# RoverBaseboard.net
KiCad netlist of a schematic drawn in EAGLE
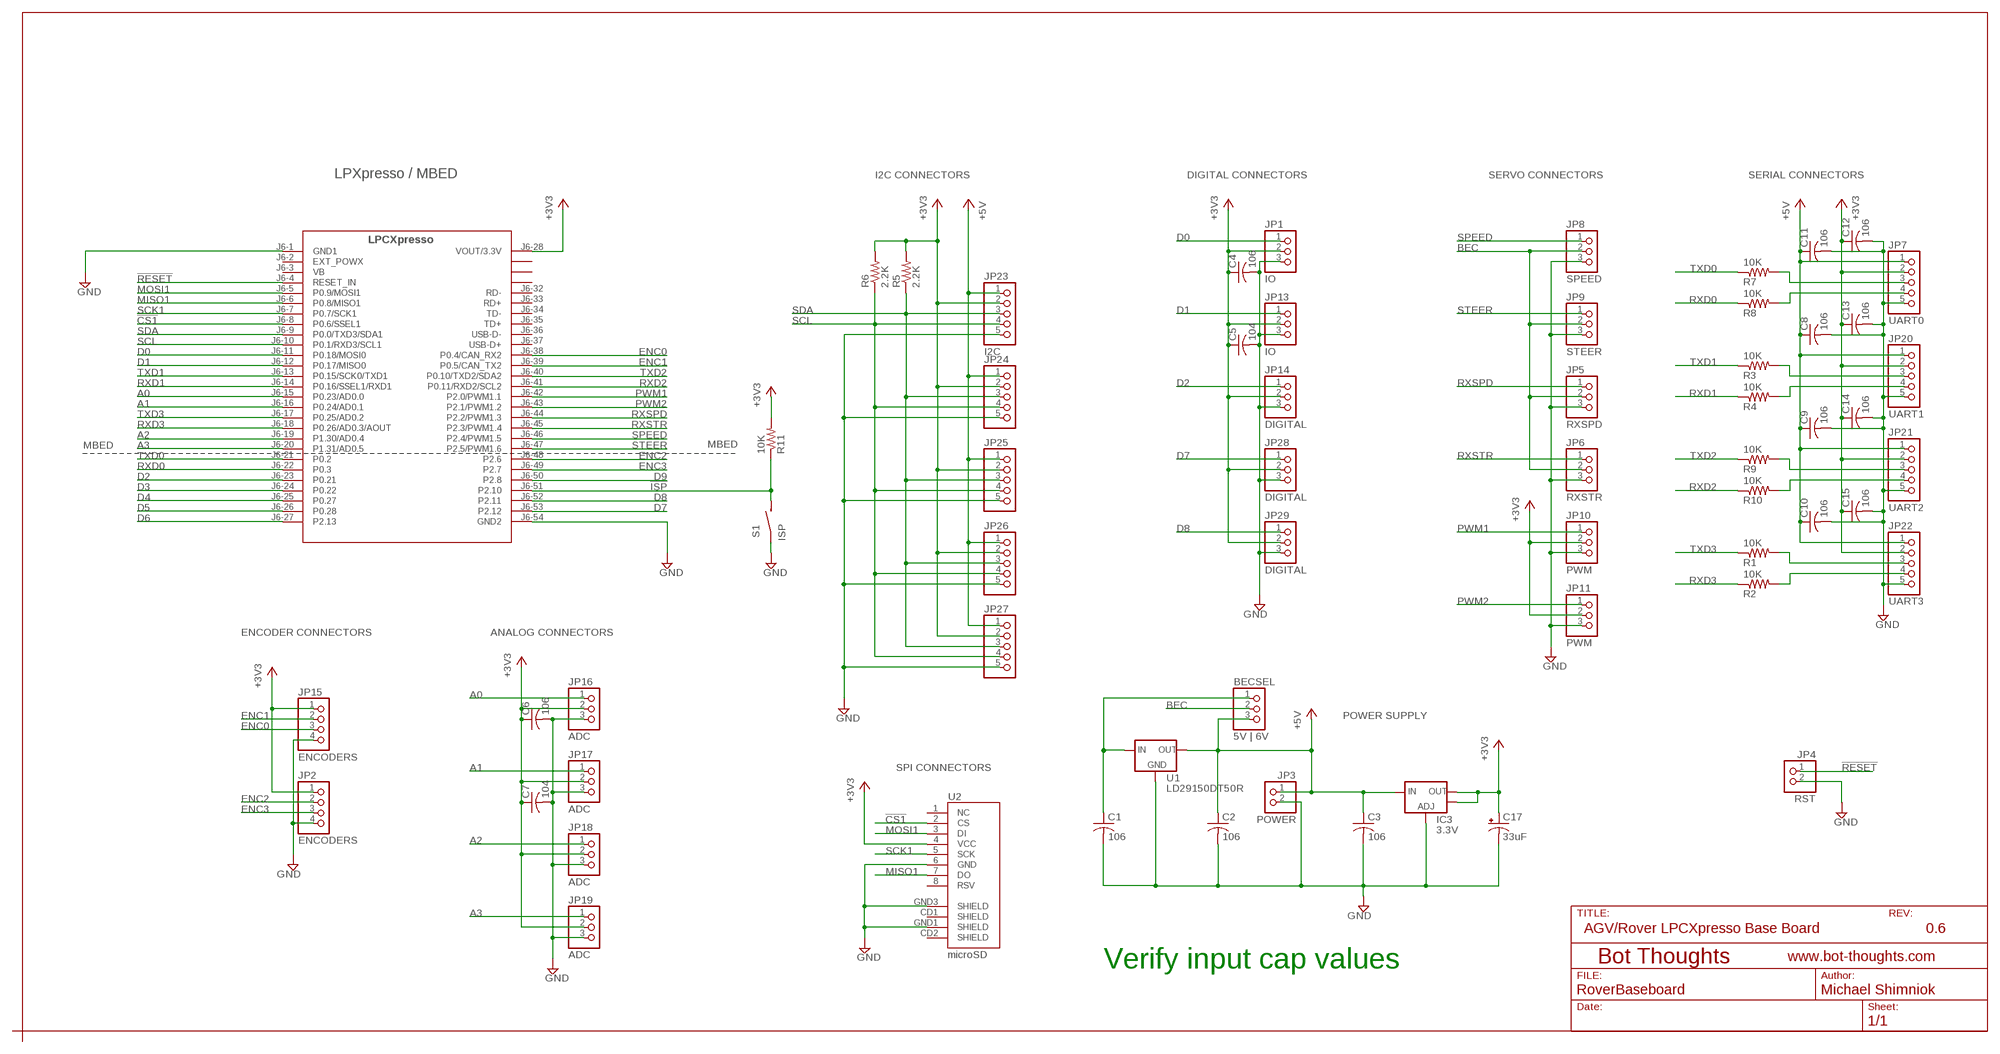
[diagram p0: schematic, sheet 1]

(export (version "E")
  (design (tool "Eeschema 10.0.6"))
  (components
    (comp (ref "BECSEL")
      (value "5V | 6V")
      (footprint "eagle-import:1X03-S")
      (libsource (lib "eagle-import") (part "PINHD-1X03_2.54-S"))
    )
    (comp (ref "C1")
      (value "106")
      (footprint "eagle-import:C1206")
      (libsource (lib "eagle-import") (part "C-USC1206"))
    )
    (comp (ref "C2")
      (value "106")
      (footprint "eagle-import:C1206")
      (libsource (lib "eagle-import") (part "C-USC1206"))
    )
    (comp (ref "C3")
      (value "106")
      (footprint "eagle-import:C1206")
      (libsource (lib "eagle-import") (part "C-USC1206"))
    )
    (comp (ref "C4")
      (value "106")
      (footprint "eagle-import:C0603")
      (libsource (lib "eagle-import") (part "C-USC0603"))
    )
    (comp (ref "C5")
      (value "104")
      (footprint "eagle-import:C0603")
      (libsource (lib "eagle-import") (part "C-USC0603"))
    )
    (comp (ref "C6")
      (value "106")
      (footprint "eagle-import:C0603")
      (libsource (lib "eagle-import") (part "C-USC0603"))
    )
    (comp (ref "C7")
      (value "104")
      (footprint "eagle-import:C0603")
      (libsource (lib "eagle-import") (part "C-USC0603"))
    )
    (comp (ref "C8")
      (value "106")
      (footprint "eagle-import:C0603")
      (libsource (lib "eagle-import") (part "C-USC0603"))
    )
    (comp (ref "C9")
      (value "106")
      (footprint "eagle-import:C0603")
      (libsource (lib "eagle-import") (part "C-USC0603"))
    )
    (comp (ref "C10")
      (value "106")
      (footprint "eagle-import:C0603")
      (libsource (lib "eagle-import") (part "C-USC0603"))
    )
    (comp (ref "C11")
      (value "106")
      (footprint "eagle-import:C0603")
      (libsource (lib "eagle-import") (part "C-USC0603"))
    )
    (comp (ref "C12")
      (value "106")
      (footprint "eagle-import:C0603")
      (libsource (lib "eagle-import") (part "C-USC0603"))
    )
    (comp (ref "C13")
      (value "106")
      (footprint "eagle-import:C0603")
      (libsource (lib "eagle-import") (part "C-USC0603"))
    )
    (comp (ref "C14")
      (value "106")
      (footprint "eagle-import:C0603")
      (libsource (lib "eagle-import") (part "C-USC0603"))
    )
    (comp (ref "C15")
      (value "106")
      (footprint "eagle-import:C0603")
      (libsource (lib "eagle-import") (part "C-USC0603"))
    )
    (comp (ref "C17")
      (value "33uF")
      (footprint "eagle-import:140CLH-0810")
      (libsource (lib "eagle-import") (part "CPOL-US140CLH-0810"))
    )
    (comp (ref "IC3")
      (value "3.3V")
      (footprint "eagle-import:SOT223")
      (libsource (lib "eagle-import") (part "V_REG_LM1117SOT223"))
    )
    (comp (ref "JP1")
      (value "IO")
      (footprint "eagle-import:1X03-S")
      (libsource (lib "eagle-import") (part "PINHD-1X03_2.54-S"))
    )
    (comp (ref "JP2")
      (value "ENCODERS")
      (footprint "eagle-import:1X04-S")
      (libsource (lib "eagle-import") (part "PINHD-1X04_2.54-S"))
    )
    (comp (ref "JP3")
      (value "POWER")
      (footprint "eagle-import:1X02-S")
      (libsource (lib "eagle-import") (part "PINHD-1X02_2.54-S"))
    )
    (comp (ref "JP4")
      (value "RST")
      (footprint "eagle-import:1X02-S")
      (libsource (lib "eagle-import") (part "PINHD-1X02_2.54-S"))
    )
    (comp (ref "JP5")
      (value "RXSPD")
      (footprint "eagle-import:1X03-S")
      (libsource (lib "eagle-import") (part "PINHD-1X03_2.54-S"))
    )
    (comp (ref "JP6")
      (value "RXSTR")
      (footprint "eagle-import:1X03-S")
      (libsource (lib "eagle-import") (part "PINHD-1X03_2.54-S"))
    )
    (comp (ref "JP7")
      (value "UART0")
      (footprint "eagle-import:1X05-S")
      (libsource (lib "eagle-import") (part "PINHD-1X05_2.54-S"))
    )
    (comp (ref "JP8")
      (value "SPEED")
      (footprint "eagle-import:1X03-S")
      (libsource (lib "eagle-import") (part "PINHD-1X03_2.54-S"))
    )
    (comp (ref "JP9")
      (value "STEER")
      (footprint "eagle-import:1X03-S")
      (libsource (lib "eagle-import") (part "PINHD-1X03_2.54-S"))
    )
    (comp (ref "JP10")
      (value "PWM")
      (footprint "eagle-import:1X03-S")
      (libsource (lib "eagle-import") (part "PINHD-1X03_2.54-S"))
    )
    (comp (ref "JP11")
      (value "PWM")
      (footprint "eagle-import:1X03-S")
      (libsource (lib "eagle-import") (part "PINHD-1X03_2.54-S"))
    )
    (comp (ref "JP13")
      (value "IO")
      (footprint "eagle-import:1X03-S")
      (libsource (lib "eagle-import") (part "PINHD-1X03_2.54-S"))
    )
    (comp (ref "JP14")
      (value "DIGITAL")
      (footprint "eagle-import:1X03-S")
      (libsource (lib "eagle-import") (part "PINHD-1X03_2.54-S"))
    )
    (comp (ref "JP15")
      (value "ENCODERS")
      (footprint "eagle-import:1X04-S")
      (libsource (lib "eagle-import") (part "PINHD-1X04_2.54-S"))
    )
    (comp (ref "JP16")
      (value "ADC")
      (footprint "eagle-import:1X03-S")
      (libsource (lib "eagle-import") (part "PINHD-1X03_2.54-S"))
    )
    (comp (ref "JP17")
      (value "ADC")
      (footprint "eagle-import:1X03-S")
      (libsource (lib "eagle-import") (part "PINHD-1X03_2.54-S"))
    )
    (comp (ref "JP18")
      (value "ADC")
      (footprint "eagle-import:1X03-S")
      (libsource (lib "eagle-import") (part "PINHD-1X03_2.54-S"))
    )
    (comp (ref "JP19")
      (value "ADC")
      (footprint "eagle-import:1X03-S")
      (libsource (lib "eagle-import") (part "PINHD-1X03_2.54-S"))
    )
    (comp (ref "JP20")
      (value "UART1")
      (footprint "eagle-import:1X05-S")
      (libsource (lib "eagle-import") (part "PINHD-1X05_2.54-S"))
    )
    (comp (ref "JP21")
      (value "UART2")
      (footprint "eagle-import:1X05-S")
      (libsource (lib "eagle-import") (part "PINHD-1X05_2.54-S"))
    )
    (comp (ref "JP22")
      (value "UART3")
      (footprint "eagle-import:1X05-S")
      (libsource (lib "eagle-import") (part "PINHD-1X05_2.54-S"))
    )
    (comp (ref "JP23")
      (value "I2C")
      (footprint "eagle-import:1X05-S")
      (libsource (lib "eagle-import") (part "PINHD-1X05_2.54-S"))
    )
    (comp (ref "JP24")
      (value "PINHD-1X05_2.54-S")
      (footprint "eagle-import:1X05-S")
      (libsource (lib "eagle-import") (part "PINHD-1X05_2.54-S"))
    )
    (comp (ref "JP25")
      (value "PINHD-1X05_2.54-S")
      (footprint "eagle-import:1X05-S")
      (libsource (lib "eagle-import") (part "PINHD-1X05_2.54-S"))
    )
    (comp (ref "JP26")
      (value "PINHD-1X05_2.54-S")
      (footprint "eagle-import:1X05-S")
      (libsource (lib "eagle-import") (part "PINHD-1X05_2.54-S"))
    )
    (comp (ref "JP27")
      (value "PINHD-1X05_2.54-S")
      (footprint "eagle-import:1X05-S")
      (libsource (lib "eagle-import") (part "PINHD-1X05_2.54-S"))
    )
    (comp (ref "JP28")
      (value "DIGITAL")
      (footprint "eagle-import:1X03-S")
      (libsource (lib "eagle-import") (part "PINHD-1X03_2.54-S"))
    )
    (comp (ref "JP29")
      (value "DIGITAL")
      (footprint "eagle-import:1X03-S")
      (libsource (lib "eagle-import") (part "PINHD-1X03_2.54-S"))
    )
    (comp (ref "R1")
      (value "10K")
      (footprint "eagle-import:R0603")
      (fields (field (name "MPN") "WCR0805-220RFI"))
      (libsource (lib "eagle-import") (part "R-US_R0603"))
    )
    (comp (ref "R2")
      (value "10K")
      (footprint "eagle-import:R0603")
      (fields (field (name "MPN") "WCR0805-220RFI"))
      (libsource (lib "eagle-import") (part "R-US_R0603"))
    )
    (comp (ref "R3")
      (value "10K")
      (footprint "eagle-import:R0603")
      (fields (field (name "MPN") "WCR0805-220RFI"))
      (libsource (lib "eagle-import") (part "R-US_R0603"))
    )
    (comp (ref "R4")
      (value "10K")
      (footprint "eagle-import:R0603")
      (fields (field (name "MPN") "WCR0805-220RFI"))
      (libsource (lib "eagle-import") (part "R-US_R0603"))
    )
    (comp (ref "R5")
      (value "2.2K")
      (footprint "eagle-import:R0603")
      (libsource (lib "eagle-import") (part "R-US_R0603"))
    )
    (comp (ref "R6")
      (value "2.2K")
      (footprint "eagle-import:R0603")
      (libsource (lib "eagle-import") (part "R-US_R0603"))
    )
    (comp (ref "R7")
      (value "10K")
      (footprint "eagle-import:R0603")
      (fields (field (name "MPN") "WCR0805-220RFI"))
      (libsource (lib "eagle-import") (part "R-US_R0603"))
    )
    (comp (ref "R8")
      (value "10K")
      (footprint "eagle-import:R0603")
      (fields (field (name "MPN") "WCR0805-220RFI"))
      (libsource (lib "eagle-import") (part "R-US_R0603"))
    )
    (comp (ref "R9")
      (value "10K")
      (footprint "eagle-import:R0603")
      (fields (field (name "MPN") "WCR0805-220RFI"))
      (libsource (lib "eagle-import") (part "R-US_R0603"))
    )
    (comp (ref "R10")
      (value "10K")
      (footprint "eagle-import:R0603")
      (fields (field (name "MPN") "WCR0805-220RFI"))
      (libsource (lib "eagle-import") (part "R-US_R0603"))
    )
    (comp (ref "R11")
      (value "10K")
      (footprint "eagle-import:R0603")
      (fields (field (name "MPN") "WCR0805-220RFI"))
      (libsource (lib "eagle-import") (part "R-US_R0603"))
    )
    (comp (ref "S1")
      (value "ISP")
      (footprint "eagle-import:6MMTACTILE_RECT")
      (libsource (lib "eagle-import") (part "SPST_TAC_RECT1"))
    )
    (comp (ref "U$1")
      (value "LPCXPRESSO")
      (footprint "eagle-import:LPCXPRESSO_NO_PAD")
      (libsource (lib "eagle-import") (part "LPCXPRESSO_NO_PAD_1768_REVB"))
    )
    (comp (ref "U1")
      (value "LD29150DT50R")
      (footprint "eagle-import:DPAK")
      (libsource (lib "eagle-import") (part "LD29150DT"))
    )
    (comp (ref "U2")
      (value "microSD")
      (footprint "eagle-import:MICRO-SD-SOCKET-PP")
      (libsource (lib "eagle-import") (part "USD-SOCKETNEW"))
    )
  )
  (nets
    (net (code "1") (name "+3V3") (class "Default")
      (node (ref "C12") (pin "1") (pinfunction "1_1") (pintype "passive"))
      (node (ref "C13") (pin "1") (pinfunction "1_1") (pintype "passive"))
      (node (ref "C14") (pin "1") (pinfunction "1_1") (pintype "passive"))
      (node (ref "C15") (pin "1") (pinfunction "1_1") (pintype "passive"))
      (node (ref "C17") (pin "+") (pinfunction "+_+") (pintype "passive"))
      (node (ref "C4") (pin "1") (pinfunction "1_1") (pintype "passive"))
      (node (ref "C5") (pin "1") (pinfunction "1_1") (pintype "passive"))
      (node (ref "C6") (pin "1") (pinfunction "1_1") (pintype "passive"))
      (node (ref "C7") (pin "1") (pinfunction "1_1") (pintype "passive"))
      (node (ref "IC3") (pin "2") (pinfunction "OUT_2") (pintype "output"))
      (node (ref "IC3") (pin "4") (pinfunction "OUT_4") (pintype "output"))
      (node (ref "JP1") (pin "2") (pinfunction "2_2") (pintype "passive"))
      (node (ref "JP10") (pin "2") (pinfunction "2_2") (pintype "passive"))
      (node (ref "JP11") (pin "2") (pinfunction "2_2") (pintype "passive"))
      (node (ref "JP13") (pin "2") (pinfunction "2_2") (pintype "passive"))
      (node (ref "JP14") (pin "2") (pinfunction "2_2") (pintype "passive"))
      (node (ref "JP15") (pin "1") (pinfunction "1_1") (pintype "passive"))
      (node (ref "JP16") (pin "2") (pinfunction "2_2") (pintype "passive"))
      (node (ref "JP17") (pin "2") (pinfunction "2_2") (pintype "passive"))
      (node (ref "JP18") (pin "2") (pinfunction "2_2") (pintype "passive"))
      (node (ref "JP19") (pin "2") (pinfunction "2_2") (pintype "passive"))
      (node (ref "JP2") (pin "1") (pinfunction "1_1") (pintype "passive"))
      (node (ref "JP20") (pin "2") (pinfunction "2_2") (pintype "passive"))
      (node (ref "JP21") (pin "2") (pinfunction "2_2") (pintype "passive"))
      (node (ref "JP22") (pin "2") (pinfunction "2_2") (pintype "passive"))
      (node (ref "JP23") (pin "2") (pinfunction "2_2") (pintype "passive"))
      (node (ref "JP24") (pin "2") (pinfunction "2_2") (pintype "passive"))
      (node (ref "JP25") (pin "2") (pinfunction "2_2") (pintype "passive"))
      (node (ref "JP26") (pin "2") (pinfunction "2_2") (pintype "passive"))
      (node (ref "JP27") (pin "2") (pinfunction "2_2") (pintype "passive"))
      (node (ref "JP28") (pin "2") (pinfunction "2_2") (pintype "passive"))
      (node (ref "JP29") (pin "2") (pinfunction "2_2") (pintype "passive"))
      (node (ref "JP7") (pin "2") (pinfunction "2_2") (pintype "passive"))
      (node (ref "R11") (pin "2") (pinfunction "2_2") (pintype "passive"))
      (node (ref "R5") (pin "2") (pinfunction "2_2") (pintype "passive"))
      (node (ref "R6") (pin "2") (pinfunction "2_2") (pintype "passive"))
      (node (ref "U$1") (pin "J6-28") (pinfunction "VOUT/3.3V_J6-28") (pintype "bidirectional"))
      (node (ref "U2") (pin "4") (pinfunction "VCC_4") (pintype "bidirectional"))
    )
    (net (code "2") (name "+5V") (class "Default")
      (node (ref "BECSEL") (pin "3") (pinfunction "3_3") (pintype "passive"))
      (node (ref "C10") (pin "1") (pinfunction "1_1") (pintype "passive"))
      (node (ref "C11") (pin "1") (pinfunction "1_1") (pintype "passive"))
      (node (ref "C2") (pin "1") (pinfunction "1_1") (pintype "passive"))
      (node (ref "C3") (pin "1") (pinfunction "1_1") (pintype "passive"))
      (node (ref "C8") (pin "1") (pinfunction "1_1") (pintype "passive"))
      (node (ref "C9") (pin "1") (pinfunction "1_1") (pintype "passive"))
      (node (ref "IC3") (pin "3") (pinfunction "IN_3") (pintype "input"))
      (node (ref "JP20") (pin "1") (pinfunction "1_1") (pintype "passive"))
      (node (ref "JP21") (pin "1") (pinfunction "1_1") (pintype "passive"))
      (node (ref "JP22") (pin "1") (pinfunction "1_1") (pintype "passive"))
      (node (ref "JP23") (pin "1") (pinfunction "1_1") (pintype "passive"))
      (node (ref "JP24") (pin "1") (pinfunction "1_1") (pintype "passive"))
      (node (ref "JP25") (pin "1") (pinfunction "1_1") (pintype "passive"))
      (node (ref "JP26") (pin "1") (pinfunction "1_1") (pintype "passive"))
      (node (ref "JP27") (pin "1") (pinfunction "1_1") (pintype "passive"))
      (node (ref "JP3") (pin "1") (pinfunction "1_1") (pintype "passive"))
      (node (ref "JP7") (pin "1") (pinfunction "1_1") (pintype "passive"))
      (node (ref "U1") (pin "3") (pinfunction "VOUT_3") (pintype "bidirectional"))
    )
    (net (code "3") (name "/A0") (class "Default")
      (node (ref "JP16") (pin "1") (pinfunction "1_1") (pintype "passive"))
      (node (ref "U$1") (pin "J6-15") (pinfunction "P0.23/AD0.0_J6-15") (pintype "bidirectional"))
    )
    (net (code "4") (name "/A1") (class "Default")
      (node (ref "JP17") (pin "1") (pinfunction "1_1") (pintype "passive"))
      (node (ref "U$1") (pin "J6-16") (pinfunction "P0.24/AD0.1_J6-16") (pintype "bidirectional"))
    )
    (net (code "5") (name "/A2") (class "Default")
      (node (ref "JP18") (pin "1") (pinfunction "1_1") (pintype "passive"))
      (node (ref "U$1") (pin "J6-19") (pinfunction "P1.30/AD0.4_J6-19") (pintype "bidirectional"))
    )
    (net (code "6") (name "/A3") (class "Default")
      (node (ref "JP19") (pin "1") (pinfunction "1_1") (pintype "passive"))
      (node (ref "U$1") (pin "J6-20") (pinfunction "P1.31/AD0.5_J6-20") (pintype "bidirectional"))
    )
    (net (code "7") (name "/BEC") (class "Default")
      (node (ref "BECSEL") (pin "2") (pinfunction "2_2") (pintype "passive"))
      (node (ref "JP5") (pin "2") (pinfunction "2_2") (pintype "passive"))
      (node (ref "JP6") (pin "2") (pinfunction "2_2") (pintype "passive"))
      (node (ref "JP8") (pin "2") (pinfunction "2_2") (pintype "passive"))
      (node (ref "JP9") (pin "2") (pinfunction "2_2") (pintype "passive"))
    )
    (net (code "8") (name "/D0") (class "Default")
      (node (ref "JP1") (pin "1") (pinfunction "1_1") (pintype "passive"))
      (node (ref "U$1") (pin "J6-11") (pinfunction "P0.18/MOSI0_J6-11") (pintype "bidirectional"))
    )
    (net (code "9") (name "/D1") (class "Default")
      (node (ref "JP13") (pin "1") (pinfunction "1_1") (pintype "passive"))
      (node (ref "U$1") (pin "J6-12") (pinfunction "P0.17/MISO0_J6-12") (pintype "bidirectional"))
    )
    (net (code "10") (name "/D2") (class "Default")
      (node (ref "JP14") (pin "1") (pinfunction "1_1") (pintype "passive"))
      (node (ref "U$1") (pin "J6-23") (pinfunction "P0.21_J6-23") (pintype "bidirectional"))
    )
    (net (code "11") (name "/D3") (class "Default")
      (node (ref "U$1") (pin "J6-24") (pinfunction "P0.22_J6-24") (pintype "bidirectional"))
    )
    (net (code "12") (name "/D4") (class "Default")
      (node (ref "U$1") (pin "J6-25") (pinfunction "P0.27_J6-25") (pintype "bidirectional"))
    )
    (net (code "13") (name "/D5") (class "Default")
      (node (ref "U$1") (pin "J6-26") (pinfunction "P0.28_J6-26") (pintype "bidirectional"))
    )
    (net (code "14") (name "/D6") (class "Default")
      (node (ref "U$1") (pin "J6-27") (pinfunction "P2.13_J6-27") (pintype "bidirectional"))
    )
    (net (code "15") (name "/D7") (class "Default")
      (node (ref "JP28") (pin "1") (pinfunction "1_1") (pintype "passive"))
      (node (ref "U$1") (pin "J6-53") (pinfunction "P2.12_J6-53") (pintype "bidirectional"))
    )
    (net (code "16") (name "/D8") (class "Default")
      (node (ref "JP29") (pin "1") (pinfunction "1_1") (pintype "passive"))
      (node (ref "U$1") (pin "J6-52") (pinfunction "P2.11_J6-52") (pintype "bidirectional"))
    )
    (net (code "17") (name "/D9") (class "Default")
      (node (ref "U$1") (pin "J6-50") (pinfunction "P2.8_J6-50") (pintype "bidirectional"))
    )
    (net (code "18") (name "/ENC0") (class "Default")
      (node (ref "JP15") (pin "3") (pinfunction "3_3") (pintype "passive"))
      (node (ref "U$1") (pin "J6-38") (pinfunction "P0.4/CAN_RX2_J6-38") (pintype "bidirectional"))
    )
    (net (code "19") (name "/ENC1") (class "Default")
      (node (ref "JP15") (pin "2") (pinfunction "2_2") (pintype "passive"))
      (node (ref "U$1") (pin "J6-39") (pinfunction "P0.5/CAN_TX2_J6-39") (pintype "bidirectional"))
    )
    (net (code "20") (name "/ENC2") (class "Default")
      (node (ref "JP2") (pin "2") (pinfunction "2_2") (pintype "passive"))
      (node (ref "U$1") (pin "J6-48") (pinfunction "P2.6_J6-48") (pintype "bidirectional"))
    )
    (net (code "21") (name "/ENC3") (class "Default")
      (node (ref "JP2") (pin "3") (pinfunction "3_3") (pintype "passive"))
      (node (ref "U$1") (pin "J6-49") (pinfunction "P2.7_J6-49") (pintype "bidirectional"))
    )
    (net (code "22") (name "/MISO1") (class "Default")
      (node (ref "U$1") (pin "J6-6") (pinfunction "P0.8/MISO1_J6-6") (pintype "bidirectional"))
      (node (ref "U2") (pin "7") (pinfunction "DO_7") (pintype "bidirectional"))
    )
    (net (code "23") (name "/MOSI1") (class "Default")
      (node (ref "U$1") (pin "J6-5") (pinfunction "P0.9/MOSI1_J6-5") (pintype "bidirectional"))
      (node (ref "U2") (pin "3") (pinfunction "DI_3") (pintype "bidirectional"))
    )
    (net (code "24") (name "/PWM1") (class "Default")
      (node (ref "JP10") (pin "1") (pinfunction "1_1") (pintype "passive"))
      (node (ref "U$1") (pin "J6-42") (pinfunction "P2.0/PWM1.1_J6-42") (pintype "bidirectional"))
    )
    (net (code "25") (name "/PWM2") (class "Default")
      (node (ref "JP11") (pin "1") (pinfunction "1_1") (pintype "passive"))
      (node (ref "U$1") (pin "J6-43") (pinfunction "P2.1/PWM1.2_J6-43") (pintype "bidirectional"))
    )
    (net (code "26") (name "/RXD0") (class "Default")
      (node (ref "R8") (pin "1") (pinfunction "1_1") (pintype "passive"))
      (node (ref "U$1") (pin "J6-22") (pinfunction "P0.3_J6-22") (pintype "bidirectional"))
    )
    (net (code "27") (name "/RXD1") (class "Default")
      (node (ref "R4") (pin "1") (pinfunction "1_1") (pintype "passive"))
      (node (ref "U$1") (pin "J6-14") (pinfunction "P0.16/SSEL1/RXD1_J6-14") (pintype "bidirectional"))
    )
    (net (code "28") (name "/RXD2") (class "Default")
      (node (ref "R10") (pin "1") (pinfunction "1_1") (pintype "passive"))
      (node (ref "U$1") (pin "J6-41") (pinfunction "P0.11/RXD2/SCL2_J6-41") (pintype "bidirectional"))
    )
    (net (code "29") (name "/RXD3") (class "Default")
      (node (ref "R2") (pin "1") (pinfunction "1_1") (pintype "passive"))
      (node (ref "U$1") (pin "J6-18") (pinfunction "P0.26/AD0.3/AOUT_J6-18") (pintype "bidirectional"))
    )
    (net (code "30") (name "/RXSPD") (class "Default")
      (node (ref "JP5") (pin "1") (pinfunction "1_1") (pintype "passive"))
      (node (ref "U$1") (pin "J6-44") (pinfunction "P2.2/PWM1.3_J6-44") (pintype "bidirectional"))
    )
    (net (code "31") (name "/RXSTR") (class "Default")
      (node (ref "JP6") (pin "1") (pinfunction "1_1") (pintype "passive"))
      (node (ref "U$1") (pin "J6-45") (pinfunction "P2.3/PWM1.4_J6-45") (pintype "bidirectional"))
    )
    (net (code "32") (name "/SCK1") (class "Default")
      (node (ref "U$1") (pin "J6-7") (pinfunction "P0.7/SCK1_J6-7") (pintype "bidirectional"))
      (node (ref "U2") (pin "5") (pinfunction "SCK_5") (pintype "bidirectional"))
    )
    (net (code "33") (name "/SCL") (class "Default")
      (node (ref "JP23") (pin "4") (pinfunction "4_4") (pintype "passive"))
      (node (ref "JP24") (pin "4") (pinfunction "4_4") (pintype "passive"))
      (node (ref "JP25") (pin "4") (pinfunction "4_4") (pintype "passive"))
      (node (ref "JP26") (pin "4") (pinfunction "4_4") (pintype "passive"))
      (node (ref "JP27") (pin "4") (pinfunction "4_4") (pintype "passive"))
      (node (ref "R6") (pin "1") (pinfunction "1_1") (pintype "passive"))
      (node (ref "U$1") (pin "J6-10") (pinfunction "P0.1/RXD3/SCL1_J6-10") (pintype "bidirectional"))
    )
    (net (code "34") (name "/SDA") (class "Default")
      (node (ref "JP23") (pin "3") (pinfunction "3_3") (pintype "passive"))
      (node (ref "JP24") (pin "3") (pinfunction "3_3") (pintype "passive"))
      (node (ref "JP25") (pin "3") (pinfunction "3_3") (pintype "passive"))
      (node (ref "JP26") (pin "3") (pinfunction "3_3") (pintype "passive"))
      (node (ref "JP27") (pin "3") (pinfunction "3_3") (pintype "passive"))
      (node (ref "R5") (pin "1") (pinfunction "1_1") (pintype "passive"))
      (node (ref "U$1") (pin "J6-9") (pinfunction "P0.0/TXD3/SDA1_J6-9") (pintype "bidirectional"))
    )
    (net (code "35") (name "/SPEED") (class "Default")
      (node (ref "JP8") (pin "1") (pinfunction "1_1") (pintype "passive"))
      (node (ref "U$1") (pin "J6-46") (pinfunction "P2.4/PWM1.5_J6-46") (pintype "bidirectional"))
    )
    (net (code "36") (name "/STEER") (class "Default")
      (node (ref "JP9") (pin "1") (pinfunction "1_1") (pintype "passive"))
      (node (ref "U$1") (pin "J6-47") (pinfunction "P2.5/PWM1.6_J6-47") (pintype "bidirectional"))
    )
    (net (code "37") (name "/TXD0") (class "Default")
      (node (ref "R7") (pin "1") (pinfunction "1_1") (pintype "passive"))
      (node (ref "U$1") (pin "J6-21") (pinfunction "P0.2_J6-21") (pintype "bidirectional"))
    )
    (net (code "38") (name "/TXD1") (class "Default")
      (node (ref "R3") (pin "1") (pinfunction "1_1") (pintype "passive"))
      (node (ref "U$1") (pin "J6-13") (pinfunction "P0.15/SCK0/TXD1_J6-13") (pintype "bidirectional"))
    )
    (net (code "39") (name "/TXD2") (class "Default")
      (node (ref "R9") (pin "1") (pinfunction "1_1") (pintype "passive"))
      (node (ref "U$1") (pin "J6-40") (pinfunction "P0.10/TXD2/SDA2_J6-40") (pintype "bidirectional"))
    )
    (net (code "40") (name "/TXD3") (class "Default")
      (node (ref "R1") (pin "1") (pinfunction "1_1") (pintype "passive"))
      (node (ref "U$1") (pin "J6-17") (pinfunction "P0.25/AD0.2_J6-17") (pintype "bidirectional"))
    )
    (net (code "41") (name "/~{CS1}") (class "Default")
      (node (ref "U$1") (pin "J6-8") (pinfunction "P0.6/SSEL1_J6-8") (pintype "bidirectional"))
      (node (ref "U2") (pin "2") (pinfunction "CS_2") (pintype "bidirectional"))
    )
    (net (code "42") (name "/~{ISP}") (class "Default")
      (node (ref "R11") (pin "1") (pinfunction "1_1") (pintype "passive"))
      (node (ref "S1") (pin "P$2") (pinfunction "S_P$2") (pintype "passive"))
      (node (ref "U$1") (pin "J6-51") (pinfunction "P2.10_J6-51") (pintype "bidirectional"))
    )
    (net (code "43") (name "/~{RESET}") (class "Default")
      (node (ref "JP4") (pin "1") (pinfunction "1_1") (pintype "passive"))
      (node (ref "U$1") (pin "J6-4") (pinfunction "RESET_IN_J6-4") (pintype "bidirectional"))
    )
    (net (code "44") (name "GND") (class "Default")
      (node (ref "C1") (pin "2") (pinfunction "2_2") (pintype "passive"))
      (node (ref "C10") (pin "2") (pinfunction "2_2") (pintype "passive"))
      (node (ref "C11") (pin "2") (pinfunction "2_2") (pintype "passive"))
      (node (ref "C12") (pin "2") (pinfunction "2_2") (pintype "passive"))
      (node (ref "C13") (pin "2") (pinfunction "2_2") (pintype "passive"))
      (node (ref "C14") (pin "2") (pinfunction "2_2") (pintype "passive"))
      (node (ref "C15") (pin "2") (pinfunction "2_2") (pintype "passive"))
      (node (ref "C17") (pin "-") (pinfunction "-_-") (pintype "passive"))
      (node (ref "C2") (pin "2") (pinfunction "2_2") (pintype "passive"))
      (node (ref "C3") (pin "2") (pinfunction "2_2") (pintype "passive"))
      (node (ref "C4") (pin "2") (pinfunction "2_2") (pintype "passive"))
      (node (ref "C5") (pin "2") (pinfunction "2_2") (pintype "passive"))
      (node (ref "C6") (pin "2") (pinfunction "2_2") (pintype "passive"))
      (node (ref "C7") (pin "2") (pinfunction "2_2") (pintype "passive"))
      (node (ref "C8") (pin "2") (pinfunction "2_2") (pintype "passive"))
      (node (ref "C9") (pin "2") (pinfunction "2_2") (pintype "passive"))
      (node (ref "IC3") (pin "1") (pinfunction "ADJ_1") (pintype "input"))
      (node (ref "JP1") (pin "3") (pinfunction "3_3") (pintype "passive"))
      (node (ref "JP10") (pin "3") (pinfunction "3_3") (pintype "passive"))
      (node (ref "JP11") (pin "3") (pinfunction "3_3") (pintype "passive"))
      (node (ref "JP13") (pin "3") (pinfunction "3_3") (pintype "passive"))
      (node (ref "JP14") (pin "3") (pinfunction "3_3") (pintype "passive"))
      (node (ref "JP15") (pin "4") (pinfunction "4_4") (pintype "passive"))
      (node (ref "JP16") (pin "3") (pinfunction "3_3") (pintype "passive"))
      (node (ref "JP17") (pin "3") (pinfunction "3_3") (pintype "passive"))
      (node (ref "JP18") (pin "3") (pinfunction "3_3") (pintype "passive"))
      (node (ref "JP19") (pin "3") (pinfunction "3_3") (pintype "passive"))
      (node (ref "JP2") (pin "4") (pinfunction "4_4") (pintype "passive"))
      (node (ref "JP20") (pin "5") (pinfunction "5_5") (pintype "passive"))
      (node (ref "JP21") (pin "5") (pinfunction "5_5") (pintype "passive"))
      (node (ref "JP22") (pin "5") (pinfunction "5_5") (pintype "passive"))
      (node (ref "JP23") (pin "5") (pinfunction "5_5") (pintype "passive"))
      (node (ref "JP24") (pin "5") (pinfunction "5_5") (pintype "passive"))
      (node (ref "JP25") (pin "5") (pinfunction "5_5") (pintype "passive"))
      (node (ref "JP26") (pin "5") (pinfunction "5_5") (pintype "passive"))
      (node (ref "JP27") (pin "5") (pinfunction "5_5") (pintype "passive"))
      (node (ref "JP28") (pin "3") (pinfunction "3_3") (pintype "passive"))
      (node (ref "JP29") (pin "3") (pinfunction "3_3") (pintype "passive"))
      (node (ref "JP3") (pin "2") (pinfunction "2_2") (pintype "passive"))
      (node (ref "JP4") (pin "2") (pinfunction "2_2") (pintype "passive"))
      (node (ref "JP5") (pin "3") (pinfunction "3_3") (pintype "passive"))
      (node (ref "JP6") (pin "3") (pinfunction "3_3") (pintype "passive"))
      (node (ref "JP7") (pin "5") (pinfunction "5_5") (pintype "passive"))
      (node (ref "JP8") (pin "3") (pinfunction "3_3") (pintype "passive"))
      (node (ref "JP9") (pin "3") (pinfunction "3_3") (pintype "passive"))
      (node (ref "S1") (pin "P$1") (pinfunction "P_P$1") (pintype "passive"))
      (node (ref "U$1") (pin "J6-1") (pinfunction "GND1_J6-1") (pintype "bidirectional"))
      (node (ref "U$1") (pin "J6-54") (pinfunction "GND2_J6-54") (pintype "bidirectional"))
      (node (ref "U1") (pin "4") (pinfunction "GND_4") (pintype "bidirectional"))
      (node (ref "U2") (pin "6") (pinfunction "GND_6") (pintype "bidirectional"))
      (node (ref "U2") (pin "GND1") (pinfunction "SHIELD_GND1") (pintype "bidirectional"))
      (node (ref "U2") (pin "GND3") (pinfunction "SHIELD_GND3") (pintype "bidirectional"))
    )
    (net (code "45") (name "Net-(JP7-Pad3)") (class "Default")
      (node (ref "JP7") (pin "3") (pinfunction "3_3") (pintype "passive"))
      (node (ref "R7") (pin "2") (pinfunction "2_2") (pintype "passive"))
    )
    (net (code "46") (name "Net-(JP7-Pad4)") (class "Default")
      (node (ref "JP7") (pin "4") (pinfunction "4_4") (pintype "passive"))
      (node (ref "R8") (pin "2") (pinfunction "2_2") (pintype "passive"))
    )
    (net (code "47") (name "Net-(JP20-Pad3)") (class "Default")
      (node (ref "JP20") (pin "3") (pinfunction "3_3") (pintype "passive"))
      (node (ref "R3") (pin "2") (pinfunction "2_2") (pintype "passive"))
    )
    (net (code "48") (name "Net-(JP20-Pad4)") (class "Default")
      (node (ref "JP20") (pin "4") (pinfunction "4_4") (pintype "passive"))
      (node (ref "R4") (pin "2") (pinfunction "2_2") (pintype "passive"))
    )
    (net (code "49") (name "Net-(JP21-Pad3)") (class "Default")
      (node (ref "JP21") (pin "3") (pinfunction "3_3") (pintype "passive"))
      (node (ref "R9") (pin "2") (pinfunction "2_2") (pintype "passive"))
    )
    (net (code "50") (name "Net-(JP21-Pad4)") (class "Default")
      (node (ref "JP21") (pin "4") (pinfunction "4_4") (pintype "passive"))
      (node (ref "R10") (pin "2") (pinfunction "2_2") (pintype "passive"))
    )
    (net (code "51") (name "Net-(JP22-Pad3)") (class "Default")
      (node (ref "JP22") (pin "3") (pinfunction "3_3") (pintype "passive"))
      (node (ref "R1") (pin "2") (pinfunction "2_2") (pintype "passive"))
    )
    (net (code "52") (name "Net-(JP22-Pad4)") (class "Default")
      (node (ref "JP22") (pin "4") (pinfunction "4_4") (pintype "passive"))
      (node (ref "R2") (pin "2") (pinfunction "2_2") (pintype "passive"))
    )
    (net (code "53") (name "Net-(U1-VIN)") (class "Default")
      (node (ref "BECSEL") (pin "1") (pinfunction "1_1") (pintype "passive"))
      (node (ref "C1") (pin "1") (pinfunction "1_1") (pintype "passive"))
      (node (ref "U1") (pin "1") (pinfunction "VIN_1") (pintype "bidirectional"))
    )
    (net (code "54") (name "unconnected-(U$1-EXT_POWX-PadJ6-2)") (class "Default")
      (node (ref "U$1") (pin "J6-2") (pinfunction "EXT_POWX_J6-2") (pintype "bidirectional"))
    )
    (net (code "55") (name "unconnected-(U$1-P$24-PadJ6-29)") (class "Default")
      (node (ref "U$1") (pin "J6-29") (pinfunction "P$24_J6-29") (pintype "no_connect"))
    )
    (net (code "56") (name "unconnected-(U$1-P$25-PadJ6-30)") (class "Default")
      (node (ref "U$1") (pin "J6-30") (pinfunction "P$25_J6-30") (pintype "no_connect"))
    )
    (net (code "57") (name "unconnected-(U$1-P$26-PadJ6-31)") (class "Default")
      (node (ref "U$1") (pin "J6-31") (pinfunction "P$26_J6-31") (pintype "no_connect"))
    )
    (net (code "58") (name "unconnected-(U$1-RD+-PadJ6-33)") (class "Default")
      (node (ref "U$1") (pin "J6-33") (pinfunction "RD+_J6-33") (pintype "bidirectional"))
    )
    (net (code "59") (name "unconnected-(U$1-RD--PadJ6-32)") (class "Default")
      (node (ref "U$1") (pin "J6-32") (pinfunction "RD-_J6-32") (pintype "bidirectional"))
    )
    (net (code "60") (name "unconnected-(U$1-TD+-PadJ6-35)") (class "Default")
      (node (ref "U$1") (pin "J6-35") (pinfunction "TD+_J6-35") (pintype "bidirectional"))
    )
    (net (code "61") (name "unconnected-(U$1-TD--PadJ6-34)") (class "Default")
      (node (ref "U$1") (pin "J6-34") (pinfunction "TD-_J6-34") (pintype "bidirectional"))
    )
    (net (code "62") (name "unconnected-(U$1-USB-D+-PadJ6-37)") (class "Default")
      (node (ref "U$1") (pin "J6-37") (pinfunction "USB-D+_J6-37") (pintype "bidirectional"))
    )
    (net (code "63") (name "unconnected-(U$1-USB-D--PadJ6-36)") (class "Default")
      (node (ref "U$1") (pin "J6-36") (pinfunction "USB-D-_J6-36") (pintype "bidirectional"))
    )
    (net (code "64") (name "unconnected-(U$1-VB-PadJ6-3)") (class "Default")
      (node (ref "U$1") (pin "J6-3") (pinfunction "VB_J6-3") (pintype "bidirectional"))
    )
    (net (code "65") (name "unconnected-(U2-NC-Pad1)") (class "Default")
      (node (ref "U2") (pin "1") (pinfunction "NC_1") (pintype "bidirectional"))
    )
    (net (code "66") (name "unconnected-(U2-RSV-Pad8)") (class "Default")
      (node (ref "U2") (pin "8") (pinfunction "RSV_8") (pintype "bidirectional"))
    )
    (net (code "67") (name "unconnected-(U2-SHIELD-PadCD1)") (class "Default")
      (node (ref "U2") (pin "CD1") (pinfunction "SHIELD_CD1") (pintype "bidirectional"))
    )
    (net (code "68") (name "unconnected-(U2-SHIELD-PadCD2)") (class "Default")
      (node (ref "U2") (pin "CD2") (pinfunction "SHIELD_CD2") (pintype "bidirectional"))
    )
  )
)
